# H-BRIDGE.net
KiCad netlist of a schematic drawn in Altium Designer
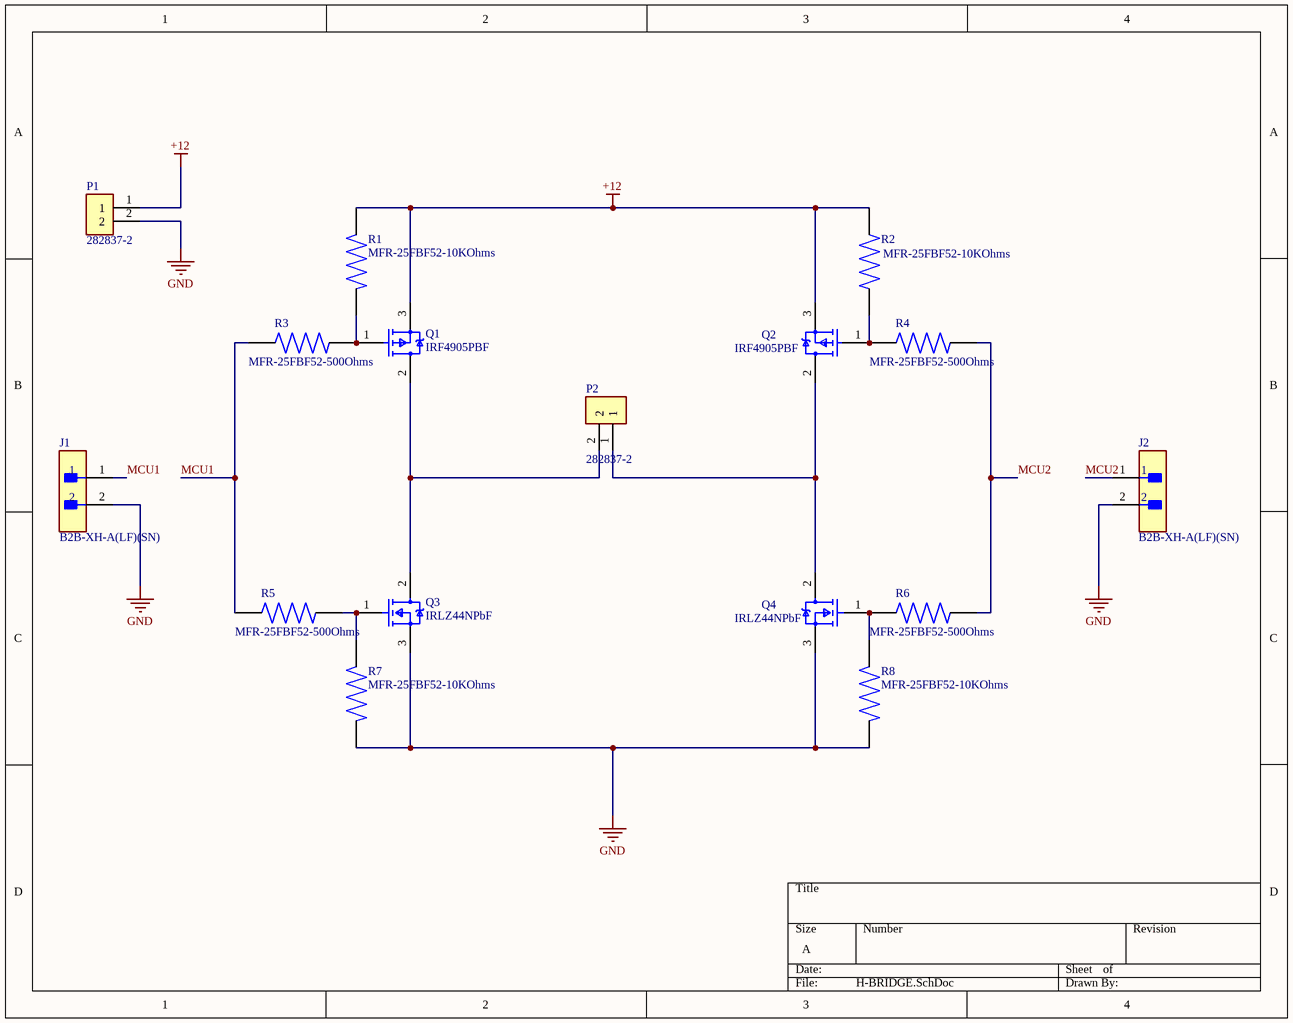
[diagram p0: H-BRIDGE.SchDoc]

(export (version "E")
  (design (tool "Eeschema 10.0.6"))
  (components
    (comp (ref "J1")
      (value "B2B-XH-A(LF)(SN)")
      (footprint "FP-B2B-XH-A_LF_SN-MFG")
      (description "CONN HEADER VERT 2POS 2.5MM")
      (libsource (lib "") (part "CMP-2000-05888-3_1"))
    )
    (comp (ref "J2")
      (value "B2B-XH-A(LF)(SN)")
      (footprint "FP-B2B-XH-A_LF_SN-MFG")
      (description "CONN HEADER VERT 2POS 2.5MM")
      (libsource (lib "Components - 07.08.24 - 10.04") (part "CMP-2000-05888-3"))
    )
    (comp (ref "P1")
      (value "282837-2")
      (footprint "TE_282837-2")
      (fields (field (name "MF") "TE Connectivity"))
      (libsource (lib "282837-2") (part "282837-2"))
    )
    (comp (ref "P2")
      (value "282837-2")
      (footprint "TE_282837-2")
      (fields (field (name "MF") "TE Connectivity"))
      (libsource (lib "") (part "282837-2_1"))
    )
    (comp (ref "Q1")
      (value "IRF4905PBF")
      (footprint "FP-PG-TO220-3-MFG")
      (description "MOSFET P-CH 55V 74A TO-220AB")
      (libsource (lib "Altium Content Vault") (part "7c43f5ccbd0f8ca8bbf61673af0f16f"))
    )
    (comp (ref "Q2")
      (value "IRF4905PBF")
      (footprint "FP-PG-TO220-3-MFG")
      (description "MOSFET P-CH 55V 74A TO-220AB")
      (libsource (lib "Altium Content Vault") (part "7c43f5ccbd0f8ca8bbf61673af0f16f"))
    )
    (comp (ref "Q3")
      (value "IRLZ44NPbF")
      (footprint "FP-PG-TO220-3-MFG")
      (description "MOSFET N-CH 55V 47A TO220AB")
      (libsource (lib "Altium Content Vault") (part "b09f7f152735e370c1ea22a33fa83d6"))
    )
    (comp (ref "Q4")
      (value "IRLZ44NPbF")
      (footprint "FP-PG-TO220-3-MFG")
      (description "MOSFET N-CH 55V 47A TO220AB")
      (libsource (lib "Altium Content Vault") (part "b09f7f152735e370c1ea22a33fa83d6"))
    )
    (comp (ref "R1")
      (value "MFR-25FBF52-10KOhms")
      (footprint "RESAD1100W55L680D260")
      (description "10.2 kOhms Â±1% 0.25W, 1/4W Through Hole Resistor Axial - Metal Film")
      (fields (field (name "MF") "Yageo") (field (name "MP") "MFR-25FBF52-10K"))
      (libsource (lib "MFR-25FBF52-10K") (part "MFR-25FBF52-10K"))
    )
    (comp (ref "R2")
      (value "MFR-25FBF52-10KOhms")
      (footprint "RESAD1100W55L680D260")
      (description "10.2 kOhms Â±1% 0.25W, 1/4W Through Hole Resistor Axial - Metal Film")
      (fields (field (name "MF") "Yageo") (field (name "MP") "MFR-25FBF52-10K"))
      (libsource (lib "MFR-25FBF52-10K") (part "MFR-25FBF52-10K"))
    )
    (comp (ref "R3")
      (value "MFR-25FBF52-500Ohms")
      (footprint "RESAD1100W55L680D260")
      (description "10.2 kOhms Â±1% 0.25W, 1/4W Through Hole Resistor Axial - Metal Film")
      (fields (field (name "MF") "Yageo") (field (name "MP") "MFR-25FBF52-10K"))
      (libsource (lib "MFR-25FBF52-10K") (part "MFR-25FBF52-10K"))
    )
    (comp (ref "R4")
      (value "MFR-25FBF52-500Ohms")
      (footprint "RESAD1100W55L680D260")
      (description "10.2 kOhms Â±1% 0.25W, 1/4W Through Hole Resistor Axial - Metal Film")
      (fields (field (name "MF") "Yageo") (field (name "MP") "MFR-25FBF52-10K"))
      (libsource (lib "MFR-25FBF52-10K") (part "MFR-25FBF52-10K"))
    )
    (comp (ref "R5")
      (value "MFR-25FBF52-500Ohms")
      (footprint "RESAD1100W55L680D260")
      (description "10.2 kOhms Â±1% 0.25W, 1/4W Through Hole Resistor Axial - Metal Film")
      (fields (field (name "MF") "Yageo") (field (name "MP") "MFR-25FBF52-10K"))
      (libsource (lib "MFR-25FBF52-10K") (part "MFR-25FBF52-10K"))
    )
    (comp (ref "R6")
      (value "MFR-25FBF52-500Ohms")
      (footprint "RESAD1100W55L680D260")
      (description "10.2 kOhms Â±1% 0.25W, 1/4W Through Hole Resistor Axial - Metal Film")
      (fields (field (name "MF") "Yageo") (field (name "MP") "MFR-25FBF52-10K"))
      (libsource (lib "MFR-25FBF52-10K") (part "MFR-25FBF52-10K"))
    )
    (comp (ref "R7")
      (value "MFR-25FBF52-10KOhms")
      (footprint "RESAD1100W55L680D260")
      (description "10.2 kOhms Â±1% 0.25W, 1/4W Through Hole Resistor Axial - Metal Film")
      (fields (field (name "MF") "Yageo") (field (name "MP") "MFR-25FBF52-10K"))
      (libsource (lib "MFR-25FBF52-10K") (part "MFR-25FBF52-10K"))
    )
    (comp (ref "R8")
      (value "MFR-25FBF52-10KOhms")
      (footprint "RESAD1100W55L680D260")
      (description "10.2 kOhms Â±1% 0.25W, 1/4W Through Hole Resistor Axial - Metal Film")
      (fields (field (name "MF") "Yageo") (field (name "MP") "MFR-25FBF52-10K"))
      (libsource (lib "MFR-25FBF52-10K") (part "MFR-25FBF52-10K"))
    )
  )
  (nets
    (net (code "1") (name "+12") (class "Default")
      (node (ref "P1") (pin "1") (pinfunction "1_1") (pintype "passive"))
      (node (ref "Q1") (pin "3") (pinfunction "SOURCE_3") (pintype "passive"))
      (node (ref "Q2") (pin "3") (pinfunction "SOURCE_3") (pintype "passive"))
      (node (ref "R1") (pin "2") (pinfunction "2_2") (pintype "passive"))
      (node (ref "R2") (pin "2") (pinfunction "2_2") (pintype "passive"))
    )
    (net (code "2") (name "/MCU1") (class "Default")
      (node (ref "J1") (pin "1") (pinfunction "1_1") (pintype "passive"))
      (node (ref "R3") (pin "1") (pinfunction "1_1") (pintype "passive"))
      (node (ref "R5") (pin "1") (pinfunction "1_1") (pintype "passive"))
    )
    (net (code "3") (name "/MCU2") (class "Default")
      (node (ref "J2") (pin "1") (pinfunction "1_1") (pintype "passive"))
      (node (ref "R4") (pin "2") (pinfunction "2_2") (pintype "passive"))
      (node (ref "R6") (pin "2") (pinfunction "2_2") (pintype "passive"))
    )
    (net (code "4") (name "GND") (class "Default")
      (node (ref "J1") (pin "2") (pinfunction "2_2") (pintype "passive"))
      (node (ref "J2") (pin "2") (pinfunction "2_2") (pintype "passive"))
      (node (ref "P1") (pin "2") (pinfunction "2_2") (pintype "passive"))
      (node (ref "Q3") (pin "3") (pinfunction "S_3") (pintype "passive"))
      (node (ref "Q4") (pin "3") (pinfunction "S_3") (pintype "passive"))
      (node (ref "R7") (pin "1") (pinfunction "1_1") (pintype "passive"))
      (node (ref "R8") (pin "1") (pinfunction "1_1") (pintype "passive"))
    )
    (net (code "5") (name "Net-(Q1-DRAIN)") (class "Default")
      (node (ref "P2") (pin "2") (pinfunction "2_2") (pintype "passive"))
      (node (ref "Q1") (pin "2") (pinfunction "DRAIN_2") (pintype "passive"))
      (node (ref "Q3") (pin "2") (pinfunction "D_2") (pintype "passive"))
    )
    (net (code "6") (name "Net-(Q1-GATE)") (class "Default")
      (node (ref "Q1") (pin "1") (pinfunction "GATE_1") (pintype "passive"))
      (node (ref "R1") (pin "1") (pinfunction "1_1") (pintype "passive"))
      (node (ref "R3") (pin "2") (pinfunction "2_2") (pintype "passive"))
    )
    (net (code "7") (name "Net-(Q2-DRAIN)") (class "Default")
      (node (ref "P2") (pin "1") (pinfunction "1_1") (pintype "passive"))
      (node (ref "Q2") (pin "2") (pinfunction "DRAIN_2") (pintype "passive"))
      (node (ref "Q4") (pin "2") (pinfunction "D_2") (pintype "passive"))
    )
    (net (code "8") (name "Net-(Q2-GATE)") (class "Default")
      (node (ref "Q2") (pin "1") (pinfunction "GATE_1") (pintype "passive"))
      (node (ref "R2") (pin "1") (pinfunction "1_1") (pintype "passive"))
      (node (ref "R4") (pin "1") (pinfunction "1_1") (pintype "passive"))
    )
    (net (code "9") (name "Net-(Q3-G)") (class "Default")
      (node (ref "Q3") (pin "1") (pinfunction "G_1") (pintype "passive"))
      (node (ref "R5") (pin "2") (pinfunction "2_2") (pintype "passive"))
      (node (ref "R7") (pin "2") (pinfunction "2_2") (pintype "passive"))
    )
    (net (code "10") (name "Net-(Q4-G)") (class "Default")
      (node (ref "Q4") (pin "1") (pinfunction "G_1") (pintype "passive"))
      (node (ref "R6") (pin "1") (pinfunction "1_1") (pintype "passive"))
      (node (ref "R8") (pin "2") (pinfunction "2_2") (pintype "passive"))
    )
  )
)
